# MIO.net
KiCad netlist of a schematic drawn in Altium Designer
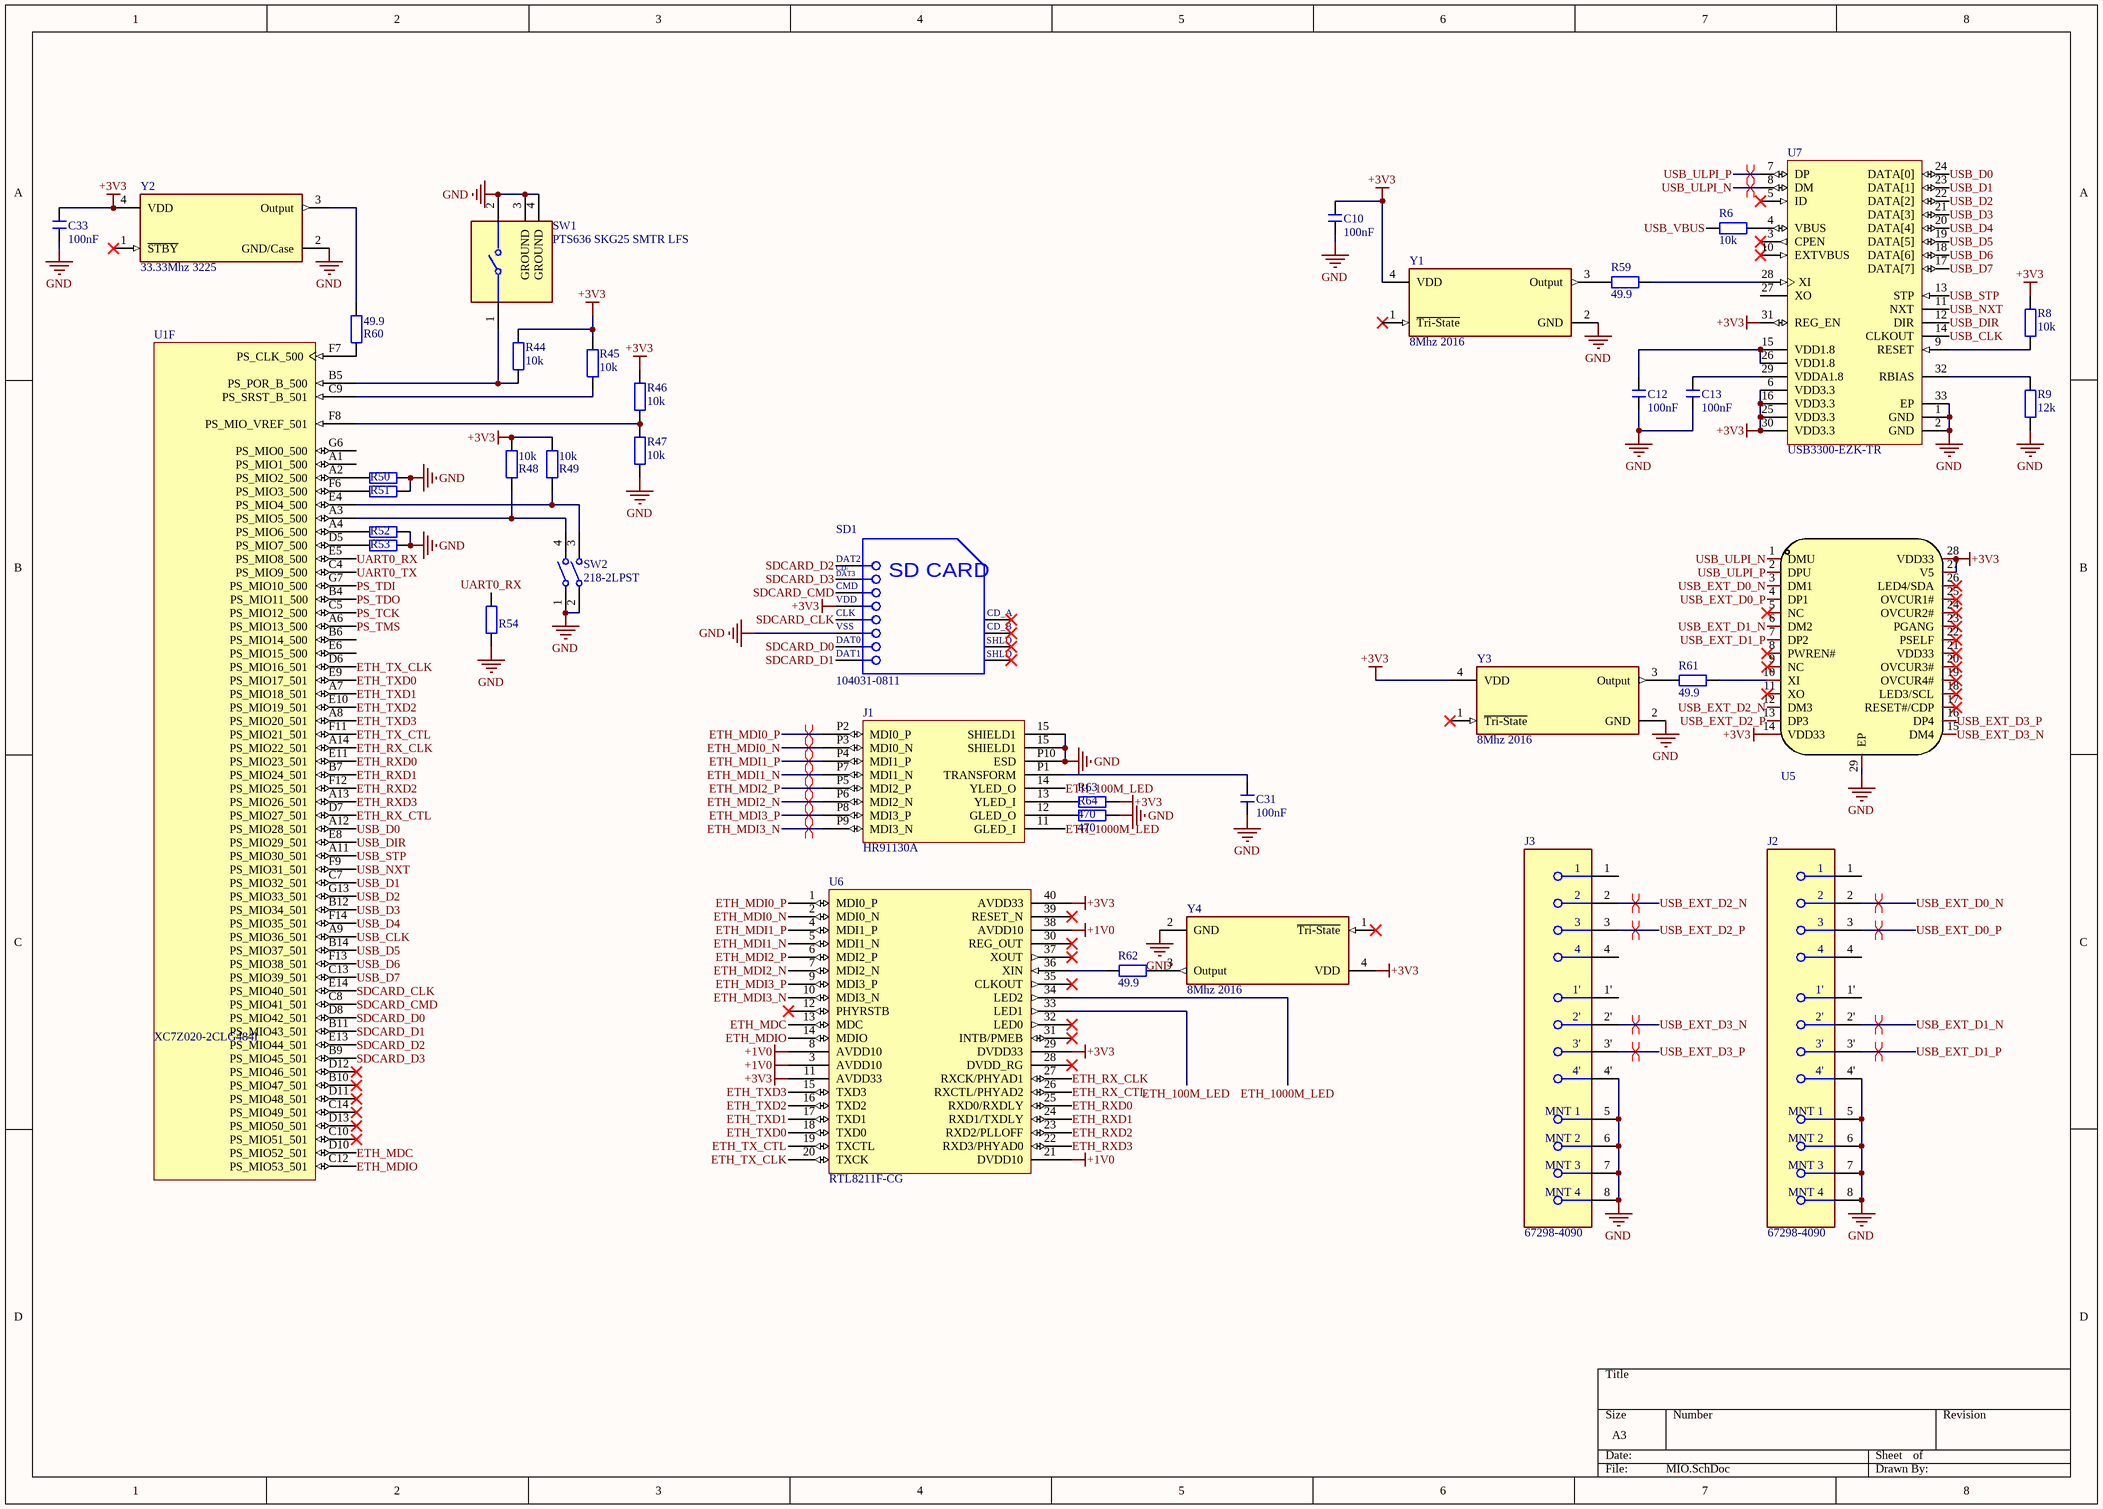
[diagram p0: MIO.SchDoc]

(export (version "E")
  (design (tool "Eeschema 10.0.6"))
  (components
    (comp (ref "C10") (value "100nF") (footprint "C0402") (libsource (lib "Passive") (part "C")))
    (comp (ref "C12") (value "100nF") (footprint "C0402") (libsource (lib "Passive") (part "C")))
    (comp (ref "C13") (value "100nF") (footprint "C0402") (libsource (lib "Passive") (part "C")))
    (comp (ref "C31") (value "100nF") (footprint "C0402") (libsource (lib "Passive") (part "C")))
    (comp (ref "C33") (value "100nF") (footprint "C0402") (libsource (lib "Passive") (part "C")))
    (comp (ref "J1")
      (value "HR91130A")
      (footprint "RJ45-TH_HR911130A")
      (description "100/1000Base-T Magnetics Single Port RJ45 Connector with Intergarted Magnetics and LED")
      (libsource (lib "Connector") (part "HR91130A"))
    )
    (comp (ref "J2")
      (value "67298-4090")
      (footprint "FP-67298-4090-MFG")
      (description "67298-4090 Conn USB 2.0 Type A RCP 8 POS 2mm/2.5mm Solder RA Thru-Hole 8 Terminal 2 Port USB Tray")
      (libsource (lib "Altium Content Vault") (part "8679bc08db72637fb1322ea8f889eff"))
    )
    (comp (ref "J3")
      (value "67298-4090")
      (footprint "FP-67298-4090-MFG")
      (description "67298-4090 Conn USB 2.0 Type A RCP 8 POS 2mm/2.5mm Solder RA Thru-Hole 8 Terminal 2 Port USB Tray")
      (libsource (lib "Altium Content Vault") (part "8679bc08db72637fb1322ea8f889eff"))
    )
    (comp (ref "R6") (value "10k") (footprint "R0402") (libsource (lib "Passive") (part "R")))
    (comp (ref "R8") (value "10k") (footprint "R0402") (libsource (lib "Passive") (part "R")))
    (comp (ref "R9") (value "12k") (footprint "R0402") (libsource (lib "Passive") (part "R")))
    (comp (ref "R44") (value "10k") (footprint "R0402") (libsource (lib "Passive") (part "R")))
    (comp (ref "R45") (value "10k") (footprint "R0402") (libsource (lib "Passive") (part "R")))
    (comp (ref "R46") (value "10k") (footprint "R0402") (libsource (lib "Passive") (part "R")))
    (comp (ref "R47") (value "10k") (footprint "R0402") (libsource (lib "Passive") (part "R")))
    (comp (ref "R48") (value "10k") (footprint "R0402") (libsource (lib "Passive") (part "R")))
    (comp (ref "R49") (value "10k") (footprint "R0402") (libsource (lib "Passive") (part "R")))
    (comp (ref "R50") (value "10k") (footprint "R0402") (libsource (lib "Passive") (part "R")))
    (comp (ref "R51") (value "10k") (footprint "R0402") (libsource (lib "Passive") (part "R")))
    (comp (ref "R52") (value "10k") (footprint "R0402") (libsource (lib "Passive") (part "R")))
    (comp (ref "R53") (value "10k") (footprint "R0402") (libsource (lib "Passive") (part "R")))
    (comp (ref "R54") (value "10k") (footprint "R0402") (libsource (lib "Passive") (part "R")))
    (comp (ref "R59") (value "49.9") (footprint "R0402") (libsource (lib "Passive") (part "R")))
    (comp (ref "R60") (value "49.9") (footprint "R0402") (libsource (lib "Passive") (part "R")))
    (comp (ref "R61") (value "49.9") (footprint "R0402") (libsource (lib "Passive") (part "R")))
    (comp (ref "R62") (value "49.9") (footprint "R0402") (libsource (lib "Passive") (part "R")))
    (comp (ref "R63") (value "470") (footprint "R0402") (libsource (lib "Passive") (part "R")))
    (comp (ref "R64") (value "470") (footprint "R0402") (libsource (lib "Passive") (part "R")))
    (comp (ref "SD1")
      (value "104031-0811")
      (footprint "MOLX-104031-0811_V")
      (description "Micro SD Card, RA, -25 to 85 degC, 8-Pin SMD, RoHS, Tape and Reel")
      (fields (field (name "MANUFACTURER") "Molex"))
      (libsource (lib "Altium Content Vault") (part "CN-SD-8-2SW-2S"))
    )
    (comp (ref "SW1")
      (value "PTS636 SKG25 SMTR LFS")
      (footprint "FP-PTS636_SKG25_SMTR_LFS-MFG")
      (description "TACT 6.0 X 3.5, 2.5 MM H, 250GF,")
      (libsource (lib "Altium Content Vault") (part "bdfe703aeb3461bf7c331fe9d798369"))
    )
    (comp (ref "SW2")
      (value "218-2LPST")
      (footprint "CTS-218-2LPST_V")
      (description "Half Pitch DIP Switch Auto Placeable, 25 mA, 24 V, -55 to 85 degC, 4-Pin SMD, RoHS, Tube")
      (fields (field (name "MANUFACTURER") "CTS Corporation"))
      (libsource (lib "Altium Content Vault") (part "SW-SPST-4_C"))
    )
    (comp (ref "U1")
      (value "XC7Z020-2CLG484I")
      (footprint "CLG484")
      (fields (field (name "GENERIC PART NUMBER") "XC7Z020"))
      (libsource (lib "Altium Content Vault") (part "XNLX-XC7Z020-CLG484"))
    )
    (comp (ref "U5")
      (value "CH334H")
      (footprint "QFN-28_L5.0-W5.0-P0.50-BL-EP")
      (fields (field (name "MANUFACTURER") "WCH(南京沁恒)"))
      (libsource (lib "WCH") (part "CH334H"))
    )
    (comp (ref "U6")
      (value "RTL8211F-CG")
      (footprint "QFN40P500X500X90_HS-41N")
      (description "INTEGRATED 10/100/1000M ETHERNET \r\nPRECISION TRANSCEIVER")
      (libsource (lib "Realtek") (part "RTL8211F-CG"))
    )
    (comp (ref "U7")
      (value "USB3300-EZK-TR")
      (footprint "MCHP-QFN-32-5x5_V2")
      (fields (field (name "GENERIC PART NUMBER") "USB3300"))
      (libsource (lib "Altium Content Vault") (part "MCHP-USB3300-QFN-32"))
    )
    (comp (ref "Y1")
      (value "8Mhz 2016")
      (footprint "FP-ASA-ASAK-MFG")
      (description "Crystal Oscillator 12.288MHz ±50ppm HCMOS 3.3V SMD 2x1.6mm")
      (libsource (lib "Altium Content Vault") (part "19c86ddd388e3e1e7fc069bbae5e46a"))
    )
    (comp (ref "Y2")
      (value "33.33Mhz 3225")
      (footprint "FP-ASE-MFG")
      (description "XTAL Oscillator 33.333MHz ±50ppm CMOS 3.3V 4-SMD 3.2mm x 2.5mm")
      (libsource (lib "Altium Content Vault") (part "61a724e6190563596ac712fef61ad37"))
    )
    (comp (ref "Y3")
      (value "8Mhz 2016")
      (footprint "FP-ASA-ASAK-MFG")
      (description "Crystal Oscillator 12.288MHz ±50ppm HCMOS 3.3V SMD 2x1.6mm")
      (libsource (lib "Altium Content Vault") (part "19c86ddd388e3e1e7fc069bbae5e46a"))
    )
    (comp (ref "Y4")
      (value "8Mhz 2016")
      (footprint "FP-ASA-ASAK-MFG")
      (description "Crystal Oscillator 12.288MHz ±50ppm HCMOS 3.3V SMD 2x1.6mm")
      (libsource (lib "") (part "19c86ddd388e3e1e7fc069bbae5e46a_1"))
    )
  )
  (nets
    (net (code "1") (name "+1V0") (class "Default")
      (node (ref "U6") (pin "21") (pinfunction "DVDD10_21") (pintype "power_in"))
      (node (ref "U6") (pin "3") (pinfunction "AVDD10_3") (pintype "power_in"))
      (node (ref "U6") (pin "38") (pinfunction "AVDD10_38") (pintype "power_in"))
      (node (ref "U6") (pin "8") (pinfunction "AVDD10_8") (pintype "power_in"))
    )
    (net (code "2") (name "+3V3") (class "Default")
      (node (ref "C10") (pin "1") (pinfunction "1_1") (pintype "passive"))
      (node (ref "C33") (pin "1") (pinfunction "1_1") (pintype "passive"))
      (node (ref "R44") (pin "1") (pinfunction "1_1") (pintype "passive"))
      (node (ref "R45") (pin "1") (pinfunction "1_1") (pintype "passive"))
      (node (ref "R46") (pin "1") (pinfunction "1_1") (pintype "passive"))
      (node (ref "R48") (pin "2") (pinfunction "2_2") (pintype "passive"))
      (node (ref "R49") (pin "2") (pinfunction "2_2") (pintype "passive"))
      (node (ref "R63") (pin "2") (pinfunction "2_2") (pintype "passive"))
      (node (ref "R8") (pin "2") (pinfunction "2_2") (pintype "passive"))
      (node (ref "SD1") (pin "4") (pinfunction "VDD_4") (pintype "passive"))
      (node (ref "U5") (pin "14") (pinfunction "VDD33_14") (pintype "passive"))
      (node (ref "U5") (pin "27") (pinfunction "V5_27") (pintype "passive"))
      (node (ref "U5") (pin "28") (pinfunction "VDD33_28") (pintype "passive"))
      (node (ref "U6") (pin "11") (pinfunction "AVDD33_11") (pintype "power_in"))
      (node (ref "U6") (pin "29") (pinfunction "DVDD33_29") (pintype "power_in"))
      (node (ref "U6") (pin "40") (pinfunction "AVDD33_40") (pintype "power_in"))
      (node (ref "U7") (pin "16") (pinfunction "VDD3.3_16") (pintype "power_in"))
      (node (ref "U7") (pin "25") (pinfunction "VDD3.3_25") (pintype "power_in"))
      (node (ref "U7") (pin "30") (pinfunction "VDD3.3_30") (pintype "power_in"))
      (node (ref "U7") (pin "31") (pinfunction "REG_EN_31") (pintype "bidirectional"))
      (node (ref "U7") (pin "6") (pinfunction "VDD3.3_6") (pintype "power_in"))
      (node (ref "Y1") (pin "4") (pinfunction "VDD_4") (pintype "power_in"))
      (node (ref "Y2") (pin "4") (pinfunction "VDD_4") (pintype "power_in"))
      (node (ref "Y3") (pin "4") (pinfunction "VDD_4") (pintype "power_in"))
      (node (ref "Y4") (pin "4") (pinfunction "VDD_4") (pintype "power_in"))
    )
    (net (code "3") (name "/ETH_100M_LED") (class "Default")
      (node (ref "J1") (pin "14") (pinfunction "YLED_O_14") (pintype "passive"))
      (node (ref "U6") (pin "33") (pinfunction "LED1_33") (pintype "output"))
    )
    (net (code "4") (name "/ETH_1000M_LED") (class "Default")
      (node (ref "J1") (pin "11") (pinfunction "GLED_I_11") (pintype "passive"))
      (node (ref "U6") (pin "34") (pinfunction "LED2_34") (pintype "output"))
    )
    (net (code "5") (name "/ETH_MDC") (class "Default")
      (node (ref "U1") (pin "D10") (pinfunction "PS_MIO52_501_D10") (pintype "bidirectional"))
      (node (ref "U6") (pin "13") (pinfunction "MDC_13") (pintype "bidirectional"))
    )
    (net (code "6") (name "/ETH_MDI0_N") (class "Default")
      (node (ref "J1") (pin "P3") (pinfunction "MDI0_N_P3") (pintype "bidirectional"))
      (node (ref "U6") (pin "2") (pinfunction "MDI0_N_2") (pintype "bidirectional"))
    )
    (net (code "7") (name "/ETH_MDI0_P") (class "Default")
      (node (ref "J1") (pin "P2") (pinfunction "MDI0_P_P2") (pintype "bidirectional"))
      (node (ref "U6") (pin "1") (pinfunction "MDI0_P_1") (pintype "bidirectional"))
    )
    (net (code "8") (name "/ETH_MDI1_N") (class "Default")
      (node (ref "J1") (pin "P7") (pinfunction "MDI1_N_P7") (pintype "bidirectional"))
      (node (ref "U6") (pin "5") (pinfunction "MDI1_N_5") (pintype "bidirectional"))
    )
    (net (code "9") (name "/ETH_MDI1_P") (class "Default")
      (node (ref "J1") (pin "P4") (pinfunction "MDI1_P_P4") (pintype "bidirectional"))
      (node (ref "U6") (pin "4") (pinfunction "MDI1_P_4") (pintype "bidirectional"))
    )
    (net (code "10") (name "/ETH_MDI2_N") (class "Default")
      (node (ref "J1") (pin "P6") (pinfunction "MDI2_N_P6") (pintype "bidirectional"))
      (node (ref "U6") (pin "7") (pinfunction "MDI2_N_7") (pintype "bidirectional"))
    )
    (net (code "11") (name "/ETH_MDI2_P") (class "Default")
      (node (ref "J1") (pin "P5") (pinfunction "MDI2_P_P5") (pintype "bidirectional"))
      (node (ref "U6") (pin "6") (pinfunction "MDI2_P_6") (pintype "bidirectional"))
    )
    (net (code "12") (name "/ETH_MDI3_N") (class "Default")
      (node (ref "J1") (pin "P9") (pinfunction "MDI3_N_P9") (pintype "bidirectional"))
      (node (ref "U6") (pin "10") (pinfunction "MDI3_N_10") (pintype "bidirectional"))
    )
    (net (code "13") (name "/ETH_MDI3_P") (class "Default")
      (node (ref "J1") (pin "P8") (pinfunction "MDI3_P_P8") (pintype "bidirectional"))
      (node (ref "U6") (pin "9") (pinfunction "MDI3_P_9") (pintype "bidirectional"))
    )
    (net (code "14") (name "/ETH_MDIO") (class "Default")
      (node (ref "U1") (pin "C12") (pinfunction "PS_MIO53_501_C12") (pintype "bidirectional"))
      (node (ref "U6") (pin "14") (pinfunction "MDIO_14") (pintype "bidirectional"))
    )
    (net (code "15") (name "/ETH_RXD0") (class "Default")
      (node (ref "U1") (pin "E11") (pinfunction "PS_MIO23_501_E11") (pintype "bidirectional"))
      (node (ref "U6") (pin "25") (pinfunction "RXD0/RXDLY_25") (pintype "bidirectional"))
    )
    (net (code "16") (name "/ETH_RXD1") (class "Default")
      (node (ref "U1") (pin "B7") (pinfunction "PS_MIO24_501_B7") (pintype "bidirectional"))
      (node (ref "U6") (pin "24") (pinfunction "RXD1/TXDLY_24") (pintype "bidirectional"))
    )
    (net (code "17") (name "/ETH_RXD2") (class "Default")
      (node (ref "U1") (pin "F12") (pinfunction "PS_MIO25_501_F12") (pintype "bidirectional"))
      (node (ref "U6") (pin "23") (pinfunction "RXD2/PLLOFF_23") (pintype "bidirectional"))
    )
    (net (code "18") (name "/ETH_RXD3") (class "Default")
      (node (ref "U1") (pin "A13") (pinfunction "PS_MIO26_501_A13") (pintype "bidirectional"))
      (node (ref "U6") (pin "22") (pinfunction "RXD3/PHYAD0_22") (pintype "bidirectional"))
    )
    (net (code "19") (name "/ETH_RX_CLK") (class "Default")
      (node (ref "U1") (pin "A14") (pinfunction "PS_MIO22_501_A14") (pintype "bidirectional"))
      (node (ref "U6") (pin "27") (pinfunction "RXCK/PHYAD1_27") (pintype "bidirectional"))
    )
    (net (code "20") (name "/ETH_RX_CTL") (class "Default")
      (node (ref "U1") (pin "D7") (pinfunction "PS_MIO27_501_D7") (pintype "bidirectional"))
      (node (ref "U6") (pin "26") (pinfunction "RXCTL/PHYAD2_26") (pintype "bidirectional"))
    )
    (net (code "21") (name "/ETH_TXD0") (class "Default")
      (node (ref "U1") (pin "E9") (pinfunction "PS_MIO17_501_E9") (pintype "bidirectional"))
      (node (ref "U6") (pin "18") (pinfunction "TXD0_18") (pintype "bidirectional"))
    )
    (net (code "22") (name "/ETH_TXD1") (class "Default")
      (node (ref "U1") (pin "A7") (pinfunction "PS_MIO18_501_A7") (pintype "bidirectional"))
      (node (ref "U6") (pin "17") (pinfunction "TXD1_17") (pintype "bidirectional"))
    )
    (net (code "23") (name "/ETH_TXD2") (class "Default")
      (node (ref "U1") (pin "E10") (pinfunction "PS_MIO19_501_E10") (pintype "bidirectional"))
      (node (ref "U6") (pin "16") (pinfunction "TXD2_16") (pintype "bidirectional"))
    )
    (net (code "24") (name "/ETH_TXD3") (class "Default")
      (node (ref "U1") (pin "A8") (pinfunction "PS_MIO20_501_A8") (pintype "bidirectional"))
      (node (ref "U6") (pin "15") (pinfunction "TXD3_15") (pintype "bidirectional"))
    )
    (net (code "25") (name "/ETH_TX_CLK") (class "Default")
      (node (ref "U1") (pin "D6") (pinfunction "PS_MIO16_501_D6") (pintype "bidirectional"))
      (node (ref "U6") (pin "20") (pinfunction "TXCK_20") (pintype "bidirectional"))
    )
    (net (code "26") (name "/ETH_TX_CTL") (class "Default")
      (node (ref "U1") (pin "F11") (pinfunction "PS_MIO21_501_F11") (pintype "bidirectional"))
      (node (ref "U6") (pin "19") (pinfunction "TXCTL_19") (pintype "bidirectional"))
    )
    (net (code "27") (name "/PS_TCK") (class "Default")
      (node (ref "U1") (pin "C5") (pinfunction "PS_MIO12_500_C5") (pintype "bidirectional"))
    )
    (net (code "28") (name "/PS_TDI") (class "Default")
      (node (ref "U1") (pin "G7") (pinfunction "PS_MIO10_500_G7") (pintype "bidirectional"))
    )
    (net (code "29") (name "/PS_TDO") (class "Default")
      (node (ref "U1") (pin "B4") (pinfunction "PS_MIO11_500_B4") (pintype "bidirectional"))
    )
    (net (code "30") (name "/PS_TMS") (class "Default")
      (node (ref "U1") (pin "A6") (pinfunction "PS_MIO13_500_A6") (pintype "bidirectional"))
    )
    (net (code "31") (name "/SDCARD_CLK") (class "Default")
      (node (ref "SD1") (pin "5") (pinfunction "CLK_5") (pintype "passive"))
      (node (ref "U1") (pin "E14") (pinfunction "PS_MIO40_501_E14") (pintype "bidirectional"))
    )
    (net (code "32") (name "/SDCARD_CMD") (class "Default")
      (node (ref "SD1") (pin "3") (pinfunction "VSS1_3") (pintype "passive"))
      (node (ref "U1") (pin "C8") (pinfunction "PS_MIO41_501_C8") (pintype "bidirectional"))
    )
    (net (code "33") (name "/SDCARD_D0") (class "Default")
      (node (ref "SD1") (pin "7") (pinfunction "DAT0_7") (pintype "passive"))
      (node (ref "U1") (pin "D8") (pinfunction "PS_MIO42_501_D8") (pintype "bidirectional"))
    )
    (net (code "34") (name "/SDCARD_D1") (class "Default")
      (node (ref "SD1") (pin "8") (pinfunction "DAT1_8") (pintype "passive"))
      (node (ref "U1") (pin "B11") (pinfunction "PS_MIO43_501_B11") (pintype "bidirectional"))
    )
    (net (code "35") (name "/SDCARD_D2") (class "Default")
      (node (ref "SD1") (pin "1") (pinfunction "CD/DAT3_1") (pintype "passive"))
      (node (ref "U1") (pin "E13") (pinfunction "PS_MIO44_501_E13") (pintype "bidirectional"))
    )
    (net (code "36") (name "/SDCARD_D3") (class "Default")
      (node (ref "SD1") (pin "2") (pinfunction "CMD_2") (pintype "passive"))
      (node (ref "U1") (pin "B9") (pinfunction "PS_MIO45_501_B9") (pintype "bidirectional"))
    )
    (net (code "37") (name "/UART0_RX") (class "Default")
      (node (ref "R54") (pin "1") (pinfunction "1_1") (pintype "passive"))
      (node (ref "U1") (pin "E5") (pinfunction "PS_MIO8_500_E5") (pintype "bidirectional"))
    )
    (net (code "38") (name "/UART0_TX") (class "Default")
      (node (ref "U1") (pin "C4") (pinfunction "PS_MIO9_500_C4") (pintype "bidirectional"))
    )
    (net (code "39") (name "/USB_CLK") (class "Default")
      (node (ref "U1") (pin "A9") (pinfunction "PS_MIO36_501_A9") (pintype "bidirectional"))
      (node (ref "U7") (pin "14") (pinfunction "CLKOUT_14") (pintype "tri_state"))
    )
    (net (code "40") (name "/USB_D0") (class "Default")
      (node (ref "U1") (pin "A12") (pinfunction "PS_MIO28_501_A12") (pintype "bidirectional"))
      (node (ref "U7") (pin "24") (pinfunction "DATA[0]_24") (pintype "bidirectional"))
    )
    (net (code "41") (name "/USB_D1") (class "Default")
      (node (ref "U1") (pin "C7") (pinfunction "PS_MIO32_501_C7") (pintype "bidirectional"))
      (node (ref "U7") (pin "23") (pinfunction "DATA[1]_23") (pintype "bidirectional"))
    )
    (net (code "42") (name "/USB_D2") (class "Default")
      (node (ref "U1") (pin "G13") (pinfunction "PS_MIO33_501_G13") (pintype "bidirectional"))
      (node (ref "U7") (pin "22") (pinfunction "DATA[2]_22") (pintype "bidirectional"))
    )
    (net (code "43") (name "/USB_D3") (class "Default")
      (node (ref "U1") (pin "B12") (pinfunction "PS_MIO34_501_B12") (pintype "bidirectional"))
      (node (ref "U7") (pin "21") (pinfunction "DATA[3]_21") (pintype "bidirectional"))
    )
    (net (code "44") (name "/USB_D4") (class "Default")
      (node (ref "U1") (pin "F14") (pinfunction "PS_MIO35_501_F14") (pintype "bidirectional"))
      (node (ref "U7") (pin "20") (pinfunction "DATA[4]_20") (pintype "bidirectional"))
    )
    (net (code "45") (name "/USB_D5") (class "Default")
      (node (ref "U1") (pin "B14") (pinfunction "PS_MIO37_501_B14") (pintype "bidirectional"))
      (node (ref "U7") (pin "19") (pinfunction "DATA[5]_19") (pintype "bidirectional"))
    )
    (net (code "46") (name "/USB_D6") (class "Default")
      (node (ref "U1") (pin "F13") (pinfunction "PS_MIO38_501_F13") (pintype "bidirectional"))
      (node (ref "U7") (pin "18") (pinfunction "DATA[6]_18") (pintype "bidirectional"))
    )
    (net (code "47") (name "/USB_D7") (class "Default")
      (node (ref "U1") (pin "C13") (pinfunction "PS_MIO39_501_C13") (pintype "bidirectional"))
      (node (ref "U7") (pin "17") (pinfunction "DATA[7]_17") (pintype "bidirectional"))
    )
    (net (code "48") (name "/USB_DIR") (class "Default")
      (node (ref "U1") (pin "E8") (pinfunction "PS_MIO29_501_E8") (pintype "bidirectional"))
      (node (ref "U7") (pin "12") (pinfunction "DIR_12") (pintype "tri_state"))
    )
    (net (code "49") (name "/USB_EXT_D0_N") (class "Default")
      (node (ref "J2") (pin "2") (pinfunction "2_2") (pintype "passive"))
      (node (ref "U5") (pin "3") (pinfunction "DM1_3") (pintype "passive"))
    )
    (net (code "50") (name "/USB_EXT_D0_P") (class "Default")
      (node (ref "J2") (pin "3") (pinfunction "3_3") (pintype "passive"))
      (node (ref "U5") (pin "4") (pinfunction "DP1_4") (pintype "passive"))
    )
    (net (code "51") (name "/USB_EXT_D1_N") (class "Default")
      (node (ref "J2") (pin "2'") (pinfunction "2'_2'") (pintype "passive"))
      (node (ref "U5") (pin "6") (pinfunction "DM2_6") (pintype "passive"))
    )
    (net (code "52") (name "/USB_EXT_D1_P") (class "Default")
      (node (ref "J2") (pin "3'") (pinfunction "3'_3'") (pintype "passive"))
      (node (ref "U5") (pin "7") (pinfunction "DP2_7") (pintype "passive"))
    )
    (net (code "53") (name "/USB_EXT_D2_N") (class "Default")
      (node (ref "J3") (pin "2") (pinfunction "2_2") (pintype "passive"))
      (node (ref "U5") (pin "12") (pinfunction "DM3_12") (pintype "passive"))
    )
    (net (code "54") (name "/USB_EXT_D2_P") (class "Default")
      (node (ref "J3") (pin "3") (pinfunction "3_3") (pintype "passive"))
      (node (ref "U5") (pin "13") (pinfunction "DP3_13") (pintype "passive"))
    )
    (net (code "55") (name "/USB_EXT_D3_N") (class "Default")
      (node (ref "J3") (pin "2'") (pinfunction "2'_2'") (pintype "passive"))
      (node (ref "U5") (pin "15") (pinfunction "DM4_15") (pintype "passive"))
    )
    (net (code "56") (name "/USB_EXT_D3_P") (class "Default")
      (node (ref "J3") (pin "3'") (pinfunction "3'_3'") (pintype "passive"))
      (node (ref "U5") (pin "16") (pinfunction "DP4_16") (pintype "passive"))
    )
    (net (code "57") (name "/USB_NXT") (class "Default")
      (node (ref "U1") (pin "F9") (pinfunction "PS_MIO31_501_F9") (pintype "bidirectional"))
      (node (ref "U7") (pin "11") (pinfunction "NXT_11") (pintype "tri_state"))
    )
    (net (code "58") (name "/USB_STP") (class "Default")
      (node (ref "U1") (pin "A11") (pinfunction "PS_MIO30_501_A11") (pintype "bidirectional"))
      (node (ref "U7") (pin "13") (pinfunction "STP_13") (pintype "input"))
    )
    (net (code "59") (name "/USB_ULPI_N") (class "Default")
      (node (ref "U5") (pin "1") (pinfunction "DMU_1") (pintype "passive"))
      (node (ref "U7") (pin "8") (pinfunction "DM_8") (pintype "bidirectional"))
    )
    (net (code "60") (name "/USB_ULPI_P") (class "Default")
      (node (ref "U5") (pin "2") (pinfunction "DPU_2") (pintype "passive"))
      (node (ref "U7") (pin "7") (pinfunction "DP_7") (pintype "bidirectional"))
    )
    (net (code "61") (name "/USB_VBUS") (class "Default")
      (node (ref "R6") (pin "2") (pinfunction "2_2") (pintype "passive"))
    )
    (net (code "62") (name "GND") (class "Default")
      (node (ref "C10") (pin "2") (pinfunction "2_2") (pintype "passive"))
      (node (ref "C12") (pin "2") (pinfunction "2_2") (pintype "passive"))
      (node (ref "C13") (pin "2") (pinfunction "2_2") (pintype "passive"))
      (node (ref "C31") (pin "2") (pinfunction "2_2") (pintype "passive"))
      (node (ref "C33") (pin "2") (pinfunction "2_2") (pintype "passive"))
      (node (ref "J1") (pin "15") (pinfunction "SHIELD1_15") (pintype "passive"))
      (node (ref "J1") (pin "P10") (pinfunction "ESD_P10") (pintype "passive"))
      (node (ref "J2") (pin "4'") (pinfunction "4'_4'") (pintype "passive"))
      (node (ref "J2") (pin "5") (pinfunction "MNT_1_5") (pintype "passive"))
      (node (ref "J2") (pin "6") (pinfunction "MNT_2_6") (pintype "passive"))
      (node (ref "J2") (pin "7") (pinfunction "MNT_3_7") (pintype "passive"))
      (node (ref "J2") (pin "8") (pinfunction "MNT_4_8") (pintype "passive"))
      (node (ref "J3") (pin "4'") (pinfunction "4'_4'") (pintype "passive"))
      (node (ref "J3") (pin "5") (pinfunction "MNT_1_5") (pintype "passive"))
      (node (ref "J3") (pin "6") (pinfunction "MNT_2_6") (pintype "passive"))
      (node (ref "J3") (pin "7") (pinfunction "MNT_3_7") (pintype "passive"))
      (node (ref "J3") (pin "8") (pinfunction "MNT_4_8") (pintype "passive"))
      (node (ref "R47") (pin "2") (pinfunction "2_2") (pintype "passive"))
      (node (ref "R50") (pin "2") (pinfunction "2_2") (pintype "passive"))
      (node (ref "R51") (pin "2") (pinfunction "2_2") (pintype "passive"))
      (node (ref "R52") (pin "2") (pinfunction "2_2") (pintype "passive"))
      (node (ref "R53") (pin "2") (pinfunction "2_2") (pintype "passive"))
      (node (ref "R54") (pin "2") (pinfunction "2_2") (pintype "passive"))
      (node (ref "R64") (pin "2") (pinfunction "2_2") (pintype "passive"))
      (node (ref "R9") (pin "1") (pinfunction "1_1") (pintype "passive"))
      (node (ref "SD1") (pin "6") (pinfunction "VSS2_6") (pintype "passive"))
      (node (ref "SW1") (pin "2") (pinfunction "2_2") (pintype "passive"))
      (node (ref "SW1") (pin "3") (pinfunction "GROUND_3") (pintype "power_in"))
      (node (ref "SW1") (pin "4") (pinfunction "GROUND_4") (pintype "power_in"))
      (node (ref "SW2") (pin "1") (pinfunction "1_1") (pintype "passive"))
      (node (ref "SW2") (pin "2") (pinfunction "2_2") (pintype "passive"))
      (node (ref "U5") (pin "29") (pinfunction "EP_29") (pintype "passive"))
      (node (ref "U7") (pin "1") (pinfunction "GND_1") (pintype "power_in"))
      (node (ref "U7") (pin "2") (pinfunction "GND_2") (pintype "power_in"))
      (node (ref "U7") (pin "33") (pinfunction "EP_33") (pintype "power_in"))
      (node (ref "Y1") (pin "2") (pinfunction "GND_2") (pintype "power_in"))
      (node (ref "Y2") (pin "2") (pinfunction "GND/Case_2") (pintype "power_in"))
      (node (ref "Y3") (pin "2") (pinfunction "GND_2") (pintype "power_in"))
      (node (ref "Y4") (pin "2") (pinfunction "GND_2") (pintype "power_in"))
    )
    (net (code "63") (name "Net-(C12-Pad1)") (class "Default")
      (node (ref "C12") (pin "1") (pinfunction "1_1") (pintype "passive"))
      (node (ref "U7") (pin "15") (pinfunction "VDD1.8_15") (pintype "power_in"))
      (node (ref "U7") (pin "26") (pinfunction "VDD1.8_26") (pintype "power_in"))
    )
    (net (code "64") (name "Net-(J1-GLED_O)") (class "Default")
      (node (ref "J1") (pin "12") (pinfunction "GLED_O_12") (pintype "passive"))
      (node (ref "R64") (pin "1") (pinfunction "1_1") (pintype "passive"))
    )
    (net (code "65") (name "Net-(J1-TRANSFORM)") (class "Default")
      (node (ref "C31") (pin "1") (pinfunction "1_1") (pintype "passive"))
      (node (ref "J1") (pin "P1") (pinfunction "TRANSFORM_P1") (pintype "passive"))
    )
    (net (code "66") (name "Net-(J1-YLED_I)") (class "Default")
      (node (ref "J1") (pin "13") (pinfunction "YLED_I_13") (pintype "passive"))
      (node (ref "R63") (pin "1") (pinfunction "1_1") (pintype "passive"))
    )
    (net (code "67") (name "Net-(U1F-PS_CLK_500)") (class "Default")
      (node (ref "R60") (pin "1") (pinfunction "1_1") (pintype "passive"))
      (node (ref "U1") (pin "F7") (pinfunction "PS_CLK_500_F7") (pintype "input"))
    )
    (net (code "68") (name "Net-(U1F-PS_MIO2_500)") (class "Default")
      (node (ref "R50") (pin "1") (pinfunction "1_1") (pintype "passive"))
      (node (ref "U1") (pin "A2") (pinfunction "PS_MIO2_500_A2") (pintype "bidirectional"))
    )
    (net (code "69") (name "Net-(U1F-PS_MIO3_500)") (class "Default")
      (node (ref "R51") (pin "1") (pinfunction "1_1") (pintype "passive"))
      (node (ref "U1") (pin "F6") (pinfunction "PS_MIO3_500_F6") (pintype "bidirectional"))
    )
    (net (code "70") (name "Net-(U1F-PS_MIO4_500)") (class "Default")
      (node (ref "R49") (pin "1") (pinfunction "1_1") (pintype "passive"))
      (node (ref "SW2") (pin "3") (pinfunction "3_3") (pintype "passive"))
      (node (ref "U1") (pin "E4") (pinfunction "PS_MIO4_500_E4") (pintype "bidirectional"))
    )
    (net (code "71") (name "Net-(U1F-PS_MIO5_500)") (class "Default")
      (node (ref "R48") (pin "1") (pinfunction "1_1") (pintype "passive"))
      (node (ref "SW2") (pin "4") (pinfunction "4_4") (pintype "passive"))
      (node (ref "U1") (pin "A3") (pinfunction "PS_MIO5_500_A3") (pintype "bidirectional"))
    )
    (net (code "72") (name "Net-(U1F-PS_MIO6_500)") (class "Default")
      (node (ref "R52") (pin "1") (pinfunction "1_1") (pintype "passive"))
      (node (ref "U1") (pin "A4") (pinfunction "PS_MIO6_500_A4") (pintype "bidirectional"))
    )
    (net (code "73") (name "Net-(U1F-PS_MIO7_500)") (class "Default")
      (node (ref "R53") (pin "1") (pinfunction "1_1") (pintype "passive"))
      (node (ref "U1") (pin "D5") (pinfunction "PS_MIO7_500_D5") (pintype "bidirectional"))
    )
    (net (code "74") (name "Net-(U1F-PS_MIO_VREF_501)") (class "Default")
      (node (ref "R46") (pin "2") (pinfunction "2_2") (pintype "passive"))
      (node (ref "R47") (pin "1") (pinfunction "1_1") (pintype "passive"))
      (node (ref "U1") (pin "F8") (pinfunction "PS_MIO_VREF_501_F8") (pintype "input"))
    )
    (net (code "75") (name "Net-(U1F-PS_POR_B_500)") (class "Default")
      (node (ref "R44") (pin "2") (pinfunction "2_2") (pintype "passive"))
      (node (ref "SW1") (pin "1") (pinfunction "1_1") (pintype "passive"))
      (node (ref "U1") (pin "B5") (pinfunction "PS_POR_B_500_B5") (pintype "input"))
    )
    (net (code "76") (name "Net-(U1F-PS_SRST_B_501)") (class "Default")
      (node (ref "R45") (pin "2") (pinfunction "2_2") (pintype "passive"))
      (node (ref "U1") (pin "C9") (pinfunction "PS_SRST_B_501_C9") (pintype "input"))
    )
    (net (code "77") (name "Net-(U5-XI)") (class "Default")
      (node (ref "R61") (pin "1") (pinfunction "1_1") (pintype "passive"))
      (node (ref "U5") (pin "10") (pinfunction "XI_10") (pintype "passive"))
    )
    (net (code "78") (name "Net-(U6-XIN)") (class "Default")
      (node (ref "R62") (pin "2") (pinfunction "2_2") (pintype "passive"))
      (node (ref "U6") (pin "36") (pinfunction "XIN_36") (pintype "input"))
    )
    (net (code "79") (name "Net-(U7-RBIAS)") (class "Default")
      (node (ref "R9") (pin "2") (pinfunction "2_2") (pintype "passive"))
      (node (ref "U7") (pin "32") (pinfunction "RBIAS_32") (pintype "passive"))
    )
    (net (code "80") (name "Net-(U7-RESET)") (class "Default")
      (node (ref "R8") (pin "1") (pinfunction "1_1") (pintype "passive"))
      (node (ref "U7") (pin "9") (pinfunction "RESET_9") (pintype "input"))
    )
    (net (code "81") (name "Net-(U7-VBUS)") (class "Default")
      (node (ref "R6") (pin "1") (pinfunction "1_1") (pintype "passive"))
      (node (ref "U7") (pin "4") (pinfunction "VBUS_4") (pintype "bidirectional"))
    )
    (net (code "82") (name "Net-(U7-VDDA1.8)") (class "Default")
      (node (ref "C13") (pin "1") (pinfunction "1_1") (pintype "passive"))
      (node (ref "U7") (pin "29") (pinfunction "VDDA1.8_29") (pintype "power_in"))
    )
    (net (code "83") (name "Net-(U7-XI)") (class "Default")
      (node (ref "R59") (pin "1") (pinfunction "1_1") (pintype "passive"))
      (node (ref "U7") (pin "28") (pinfunction "XI_28") (pintype "input"))
    )
    (net (code "84") (name "Net-(Y1-Output)") (class "Default")
      (node (ref "R59") (pin "2") (pinfunction "2_2") (pintype "passive"))
      (node (ref "Y1") (pin "3") (pinfunction "Output_3") (pintype "output"))
    )
    (net (code "85") (name "Net-(Y2-Output)") (class "Default")
      (node (ref "R60") (pin "2") (pinfunction "2_2") (pintype "passive"))
      (node (ref "Y2") (pin "3") (pinfunction "Output_3") (pintype "output"))
    )
    (net (code "86") (name "Net-(Y3-Output)") (class "Default")
      (node (ref "R61") (pin "2") (pinfunction "2_2") (pintype "passive"))
      (node (ref "Y3") (pin "3") (pinfunction "Output_3") (pintype "output"))
    )
    (net (code "87") (name "Net-(Y4-Output)") (class "Default")
      (node (ref "R62") (pin "1") (pinfunction "1_1") (pintype "passive"))
      (node (ref "Y4") (pin "3") (pinfunction "Output_3") (pintype "output"))
    )
    (net (code "88") (name "unconnected-(J2-Pad1')") (class "Default")
      (node (ref "J2") (pin "1'") (pinfunction "1'_1'") (pintype "passive"))
    )
    (net (code "89") (name "unconnected-(J2-Pad1)") (class "Default")
      (node (ref "J2") (pin "1") (pinfunction "1_1") (pintype "passive"))
    )
    (net (code "90") (name "unconnected-(J2-Pad4)") (class "Default")
      (node (ref "J2") (pin "4") (pinfunction "4_4") (pintype "passive"))
    )
    (net (code "91") (name "unconnected-(J3-Pad1')") (class "Default")
      (node (ref "J3") (pin "1'") (pinfunction "1'_1'") (pintype "passive"))
    )
    (net (code "92") (name "unconnected-(J3-Pad1)") (class "Default")
      (node (ref "J3") (pin "1") (pinfunction "1_1") (pintype "passive"))
    )
    (net (code "93") (name "unconnected-(J3-Pad4)") (class "Default")
      (node (ref "J3") (pin "4") (pinfunction "4_4") (pintype "passive"))
    )
    (net (code "94") (name "unconnected-(SD1-CD_A-Pad9)") (class "Default")
      (node (ref "SD1") (pin "9") (pinfunction "CD_A_9") (pintype "passive+no_connect"))
    )
    (net (code "95") (name "unconnected-(SD1-CD_B-Pad10)") (class "Default")
      (node (ref "SD1") (pin "10") (pinfunction "CD_B_10") (pintype "passive+no_connect"))
    )
    (net (code "96") (name "unconnected-(SD1-SHLD1-Pad11)") (class "Default")
      (node (ref "SD1") (pin "11") (pinfunction "SHLD1_11") (pintype "passive+no_connect"))
    )
    (net (code "97") (name "unconnected-(SD1-SHLD2-Pad12)") (class "Default")
      (node (ref "SD1") (pin "12") (pinfunction "SHLD2_12") (pintype "passive+no_connect"))
    )
    (net (code "98") (name "unconnected-(U1F-PS_MIO0_500-PadG6)") (class "Default")
      (node (ref "U1") (pin "G6") (pinfunction "PS_MIO0_500_G6") (pintype "bidirectional"))
    )
    (net (code "99") (name "unconnected-(U1F-PS_MIO1_500-PadA1)") (class "Default")
      (node (ref "U1") (pin "A1") (pinfunction "PS_MIO1_500_A1") (pintype "bidirectional"))
    )
    (net (code "100") (name "unconnected-(U1F-PS_MIO14_500-PadB6)") (class "Default")
      (node (ref "U1") (pin "B6") (pinfunction "PS_MIO14_500_B6") (pintype "bidirectional"))
    )
    (net (code "101") (name "unconnected-(U1F-PS_MIO15_500-PadE6)") (class "Default")
      (node (ref "U1") (pin "E6") (pinfunction "PS_MIO15_500_E6") (pintype "bidirectional"))
    )
    (net (code "102") (name "unconnected-(U1F-PS_MIO46_501-PadD12)") (class "Default")
      (node (ref "U1") (pin "D12") (pinfunction "PS_MIO46_501_D12") (pintype "bidirectional+no_connect"))
    )
    (net (code "103") (name "unconnected-(U1F-PS_MIO47_501-PadB10)") (class "Default")
      (node (ref "U1") (pin "B10") (pinfunction "PS_MIO47_501_B10") (pintype "bidirectional+no_connect"))
    )
    (net (code "104") (name "unconnected-(U1F-PS_MIO48_501-PadD11)") (class "Default")
      (node (ref "U1") (pin "D11") (pinfunction "PS_MIO48_501_D11") (pintype "bidirectional+no_connect"))
    )
    (net (code "105") (name "unconnected-(U1F-PS_MIO49_501-PadC14)") (class "Default")
      (node (ref "U1") (pin "C14") (pinfunction "PS_MIO49_501_C14") (pintype "bidirectional+no_connect"))
    )
    (net (code "106") (name "unconnected-(U1F-PS_MIO50_501-PadD13)") (class "Default")
      (node (ref "U1") (pin "D13") (pinfunction "PS_MIO50_501_D13") (pintype "bidirectional+no_connect"))
    )
    (net (code "107") (name "unconnected-(U1F-PS_MIO51_501-PadC10)") (class "Default")
      (node (ref "U1") (pin "C10") (pinfunction "PS_MIO51_501_C10") (pintype "bidirectional+no_connect"))
    )
    (net (code "108") (name "unconnected-(U5-LED3{slash}SCL-Pad18)") (class "Default")
      (node (ref "U5") (pin "18") (pinfunction "LED3/SCL_18") (pintype "passive+no_connect"))
    )
    (net (code "109") (name "unconnected-(U5-LED4{slash}SDA-Pad26)") (class "Default")
      (node (ref "U5") (pin "26") (pinfunction "LED4/SDA_26") (pintype "passive+no_connect"))
    )
    (net (code "110") (name "unconnected-(U5-NC-Pad5)") (class "Default")
      (node (ref "U5") (pin "5") (pinfunction "NC_5") (pintype "passive+no_connect"))
    )
    (net (code "111") (name "unconnected-(U5-NC-Pad9)") (class "Default")
      (node (ref "U5") (pin "9") (pinfunction "NC_9") (pintype "passive+no_connect"))
    )
    (net (code "112") (name "unconnected-(U5-OVCUR1#-Pad25)") (class "Default")
      (node (ref "U5") (pin "25") (pinfunction "OVCUR1#_25") (pintype "passive+no_connect"))
    )
    (net (code "113") (name "unconnected-(U5-OVCUR2#-Pad24)") (class "Default")
      (node (ref "U5") (pin "24") (pinfunction "OVCUR2#_24") (pintype "passive+no_connect"))
    )
    (net (code "114") (name "unconnected-(U5-OVCUR3#-Pad20)") (class "Default")
      (node (ref "U5") (pin "20") (pinfunction "OVCUR3#_20") (pintype "passive+no_connect"))
    )
    (net (code "115") (name "unconnected-(U5-OVCUR4#-Pad19)") (class "Default")
      (node (ref "U5") (pin "19") (pinfunction "OVCUR4#_19") (pintype "passive+no_connect"))
    )
    (net (code "116") (name "unconnected-(U5-PGANG-Pad23)") (class "Default")
      (node (ref "U5") (pin "23") (pinfunction "PGANG_23") (pintype "passive+no_connect"))
    )
    (net (code "117") (name "unconnected-(U5-PSELF-Pad22)") (class "Default")
      (node (ref "U5") (pin "22") (pinfunction "PSELF_22") (pintype "passive+no_connect"))
    )
    (net (code "118") (name "unconnected-(U5-PWREN#-Pad8)") (class "Default")
      (node (ref "U5") (pin "8") (pinfunction "PWREN#_8") (pintype "passive+no_connect"))
    )
    (net (code "119") (name "unconnected-(U5-RESET#{slash}CDP-Pad17)") (class "Default")
      (node (ref "U5") (pin "17") (pinfunction "RESET#/CDP_17") (pintype "passive+no_connect"))
    )
    (net (code "120") (name "unconnected-(U5-VDD33-Pad21)") (class "Default")
      (node (ref "U5") (pin "21") (pinfunction "VDD33_21") (pintype "passive+no_connect"))
    )
    (net (code "121") (name "unconnected-(U5-XO-Pad11)") (class "Default")
      (node (ref "U5") (pin "11") (pinfunction "XO_11") (pintype "passive+no_connect"))
    )
    (net (code "122") (name "unconnected-(U6-CLKOUT-Pad35)") (class "Default")
      (node (ref "U6") (pin "35") (pinfunction "CLKOUT_35") (pintype "output+no_connect"))
    )
    (net (code "123") (name "unconnected-(U6-DVDD_RG-Pad28)") (class "Default")
      (node (ref "U6") (pin "28") (pinfunction "DVDD_RG_28") (pintype "power_in+no_connect"))
    )
    (net (code "124") (name "unconnected-(U6-INTB{slash}PMEB-Pad31)") (class "Default")
      (node (ref "U6") (pin "31") (pinfunction "INTB/PMEB_31") (pintype "bidirectional+no_connect"))
    )
    (net (code "125") (name "unconnected-(U6-LED0-Pad32)") (class "Default")
      (node (ref "U6") (pin "32") (pinfunction "LED0_32") (pintype "output+no_connect"))
    )
    (net (code "126") (name "unconnected-(U6-PHYRSTB-Pad12)") (class "Default")
      (node (ref "U6") (pin "12") (pinfunction "PHYRSTB_12") (pintype "bidirectional+no_connect"))
    )
    (net (code "127") (name "unconnected-(U6-REG_OUT-Pad30)") (class "Default")
      (node (ref "U6") (pin "30") (pinfunction "REG_OUT_30") (pintype "open_emitter+no_connect"))
    )
    (net (code "128") (name "unconnected-(U6-RESET_N-Pad39)") (class "Default")
      (node (ref "U6") (pin "39") (pinfunction "RESET_N_39") (pintype "passive+no_connect"))
    )
    (net (code "129") (name "unconnected-(U6-XOUT-Pad37)") (class "Default")
      (node (ref "U6") (pin "37") (pinfunction "XOUT_37") (pintype "output+no_connect"))
    )
    (net (code "130") (name "unconnected-(U7-CPEN-Pad3)") (class "Default")
      (node (ref "U7") (pin "3") (pinfunction "CPEN_3") (pintype "output+no_connect"))
    )
    (net (code "131") (name "unconnected-(U7-EXTVBUS-Pad10)") (class "Default")
      (node (ref "U7") (pin "10") (pinfunction "EXTVBUS_10") (pintype "input+no_connect"))
    )
    (net (code "132") (name "unconnected-(U7-ID-Pad5)") (class "Default")
      (node (ref "U7") (pin "5") (pinfunction "ID_5") (pintype "input+no_connect"))
    )
    (net (code "133") (name "unconnected-(U7-XO-Pad27)") (class "Default")
      (node (ref "U7") (pin "27") (pinfunction "XO_27") (pintype "passive"))
    )
    (net (code "134") (name "unconnected-(Y1-~{Tri-State}-Pad1)") (class "Default")
      (node (ref "Y1") (pin "1") (pinfunction "~{Tri-State}_1") (pintype "input+no_connect"))
    )
    (net (code "135") (name "unconnected-(Y2-~{STBY}-Pad1)") (class "Default")
      (node (ref "Y2") (pin "1") (pinfunction "~{STBY}_1") (pintype "input+no_connect"))
    )
    (net (code "136") (name "unconnected-(Y3-~{Tri-State}-Pad1)") (class "Default")
      (node (ref "Y3") (pin "1") (pinfunction "~{Tri-State}_1") (pintype "input+no_connect"))
    )
    (net (code "137") (name "unconnected-(Y4-~{Tri-State}-Pad1)") (class "Default")
      (node (ref "Y4") (pin "1") (pinfunction "~{Tri-State}_1") (pintype "input+no_connect"))
    )
  )
)
